# HV_MPPC.net
KiCad netlist of a schematic drawn in EAGLE
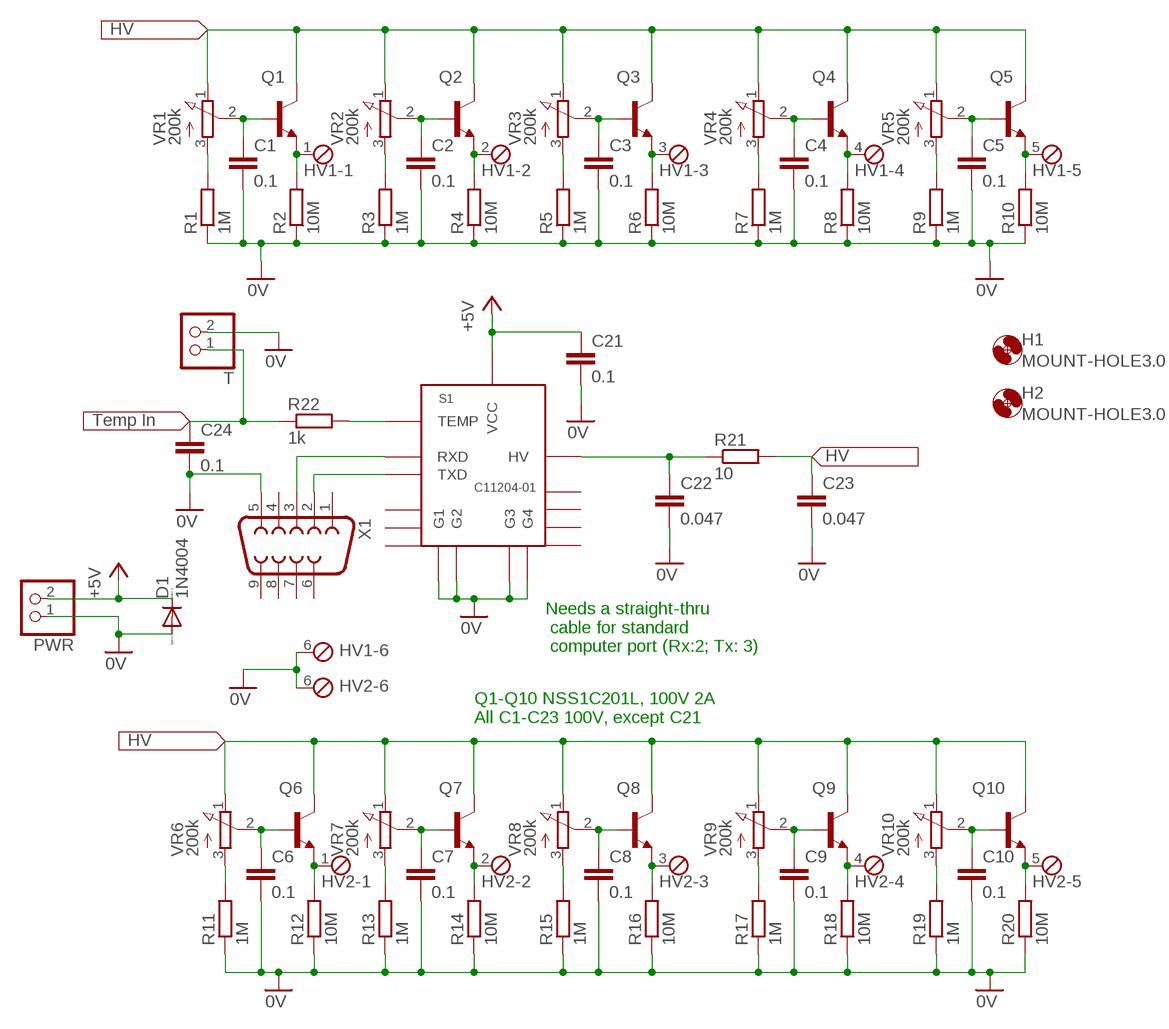
[diagram p0: schematic, sheet 1]

(export (version "E")
  (design (tool "Eeschema 10.0.6"))
  (components
    (comp (ref "C1")
      (value "0.1")
      (footprint "eagle-import:C0805")
      (libsource (lib "eagle-import") (part "C-EUC0805"))
    )
    (comp (ref "C2")
      (value "0.1")
      (footprint "eagle-import:C0805")
      (libsource (lib "eagle-import") (part "C-EUC0805"))
    )
    (comp (ref "C3")
      (value "0.1")
      (footprint "eagle-import:C0805")
      (libsource (lib "eagle-import") (part "C-EUC0805"))
    )
    (comp (ref "C4")
      (value "0.1")
      (footprint "eagle-import:C0805")
      (libsource (lib "eagle-import") (part "C-EUC0805"))
    )
    (comp (ref "C5")
      (value "0.1")
      (footprint "eagle-import:C0805")
      (libsource (lib "eagle-import") (part "C-EUC0805"))
    )
    (comp (ref "C6")
      (value "0.1")
      (footprint "eagle-import:C0805")
      (libsource (lib "eagle-import") (part "C-EUC0805"))
    )
    (comp (ref "C7")
      (value "0.1")
      (footprint "eagle-import:C0805")
      (libsource (lib "eagle-import") (part "C-EUC0805"))
    )
    (comp (ref "C8")
      (value "0.1")
      (footprint "eagle-import:C0805")
      (libsource (lib "eagle-import") (part "C-EUC0805"))
    )
    (comp (ref "C9")
      (value "0.1")
      (footprint "eagle-import:C0805")
      (libsource (lib "eagle-import") (part "C-EUC0805"))
    )
    (comp (ref "C10")
      (value "0.1")
      (footprint "eagle-import:C0805")
      (libsource (lib "eagle-import") (part "C-EUC0805"))
    )
    (comp (ref "C21")
      (value "0.1")
      (footprint "eagle-import:C0805")
      (libsource (lib "eagle-import") (part "C-EUC0805"))
    )
    (comp (ref "C22")
      (value "0.047")
      (footprint "eagle-import:C0805")
      (libsource (lib "eagle-import") (part "C-EUC0805"))
    )
    (comp (ref "C23")
      (value "0.047")
      (footprint "eagle-import:C0805")
      (libsource (lib "eagle-import") (part "C-EUC0805"))
    )
    (comp (ref "C24")
      (value "0.1")
      (footprint "eagle-import:C0805")
      (libsource (lib "eagle-import") (part "C-EUC0805"))
    )
    (comp (ref "D1")
      (value "1N4004")
      (footprint "eagle-import:DO41-10")
      (libsource (lib "eagle-import") (part "1N4004"))
    )
    (comp (ref "H1")
      (value "MOUNT-HOLE3.0")
      (footprint "eagle-import:3,0")
      (libsource (lib "eagle-import") (part "MOUNT-HOLE3.0"))
    )
    (comp (ref "H2")
      (value "MOUNT-HOLE3.0")
      (footprint "eagle-import:3,0")
      (libsource (lib "eagle-import") (part "MOUNT-HOLE3.0"))
    )
    (comp (ref "HV1")
      (value "MPT6")
      (footprint "eagle-import:6POL254")
      (libsource (lib "eagle-import") (part "MPT6"))
    )
    (comp (ref "HV2")
      (value "MPT6")
      (footprint "eagle-import:6POL254")
      (libsource (lib "eagle-import") (part "MPT6"))
    )
    (comp (ref "PWR")
      (value "PINHD-1X2")
      (footprint "eagle-import:1X02")
      (libsource (lib "eagle-import") (part "PINHD-1X2"))
    )
    (comp (ref "Q1")
      (value "NSS1C201L")
      (footprint "eagle-import:SOT23")
      (libsource (lib "eagle-import") (part "NSS1C201L"))
    )
    (comp (ref "Q2")
      (value "NSS1C201L")
      (footprint "eagle-import:SOT23")
      (libsource (lib "eagle-import") (part "NSS1C201L"))
    )
    (comp (ref "Q3")
      (value "NSS1C201L")
      (footprint "eagle-import:SOT23")
      (libsource (lib "eagle-import") (part "NSS1C201L"))
    )
    (comp (ref "Q4")
      (value "NSS1C201L")
      (footprint "eagle-import:SOT23")
      (libsource (lib "eagle-import") (part "NSS1C201L"))
    )
    (comp (ref "Q5")
      (value "NSS1C201L")
      (footprint "eagle-import:SOT23")
      (libsource (lib "eagle-import") (part "NSS1C201L"))
    )
    (comp (ref "Q6")
      (value "NSS1C201L")
      (footprint "eagle-import:SOT23")
      (libsource (lib "eagle-import") (part "NSS1C201L"))
    )
    (comp (ref "Q7")
      (value "NSS1C201L")
      (footprint "eagle-import:SOT23")
      (libsource (lib "eagle-import") (part "NSS1C201L"))
    )
    (comp (ref "Q8")
      (value "NSS1C201L")
      (footprint "eagle-import:SOT23")
      (libsource (lib "eagle-import") (part "NSS1C201L"))
    )
    (comp (ref "Q9")
      (value "NSS1C201L")
      (footprint "eagle-import:SOT23")
      (libsource (lib "eagle-import") (part "NSS1C201L"))
    )
    (comp (ref "Q10")
      (value "NSS1C201L")
      (footprint "eagle-import:SOT23")
      (libsource (lib "eagle-import") (part "NSS1C201L"))
    )
    (comp (ref "R1")
      (value "1M")
      (footprint "eagle-import:R0805")
      (libsource (lib "eagle-import") (part "R-EU_R0805"))
    )
    (comp (ref "R2")
      (value "10M")
      (footprint "eagle-import:R0805")
      (libsource (lib "eagle-import") (part "R-EU_R0805"))
    )
    (comp (ref "R3")
      (value "1M")
      (footprint "eagle-import:R0805")
      (libsource (lib "eagle-import") (part "R-EU_R0805"))
    )
    (comp (ref "R4")
      (value "10M")
      (footprint "eagle-import:R0805")
      (libsource (lib "eagle-import") (part "R-EU_R0805"))
    )
    (comp (ref "R5")
      (value "1M")
      (footprint "eagle-import:R0805")
      (libsource (lib "eagle-import") (part "R-EU_R0805"))
    )
    (comp (ref "R6")
      (value "10M")
      (footprint "eagle-import:R0805")
      (libsource (lib "eagle-import") (part "R-EU_R0805"))
    )
    (comp (ref "R7")
      (value "1M")
      (footprint "eagle-import:R0805")
      (libsource (lib "eagle-import") (part "R-EU_R0805"))
    )
    (comp (ref "R8")
      (value "10M")
      (footprint "eagle-import:R0805")
      (libsource (lib "eagle-import") (part "R-EU_R0805"))
    )
    (comp (ref "R9")
      (value "1M")
      (footprint "eagle-import:R0805")
      (libsource (lib "eagle-import") (part "R-EU_R0805"))
    )
    (comp (ref "R10")
      (value "10M")
      (footprint "eagle-import:R0805")
      (libsource (lib "eagle-import") (part "R-EU_R0805"))
    )
    (comp (ref "R11")
      (value "1M")
      (footprint "eagle-import:R0805")
      (libsource (lib "eagle-import") (part "R-EU_R0805"))
    )
    (comp (ref "R12")
      (value "10M")
      (footprint "eagle-import:R0805")
      (libsource (lib "eagle-import") (part "R-EU_R0805"))
    )
    (comp (ref "R13")
      (value "1M")
      (footprint "eagle-import:R0805")
      (libsource (lib "eagle-import") (part "R-EU_R0805"))
    )
    (comp (ref "R14")
      (value "10M")
      (footprint "eagle-import:R0805")
      (libsource (lib "eagle-import") (part "R-EU_R0805"))
    )
    (comp (ref "R15")
      (value "1M")
      (footprint "eagle-import:R0805")
      (libsource (lib "eagle-import") (part "R-EU_R0805"))
    )
    (comp (ref "R16")
      (value "10M")
      (footprint "eagle-import:R0805")
      (libsource (lib "eagle-import") (part "R-EU_R0805"))
    )
    (comp (ref "R17")
      (value "1M")
      (footprint "eagle-import:R0805")
      (libsource (lib "eagle-import") (part "R-EU_R0805"))
    )
    (comp (ref "R18")
      (value "10M")
      (footprint "eagle-import:R0805")
      (libsource (lib "eagle-import") (part "R-EU_R0805"))
    )
    (comp (ref "R19")
      (value "1M")
      (footprint "eagle-import:R0805")
      (libsource (lib "eagle-import") (part "R-EU_R0805"))
    )
    (comp (ref "R20")
      (value "10M")
      (footprint "eagle-import:R0805")
      (libsource (lib "eagle-import") (part "R-EU_R0805"))
    )
    (comp (ref "R21")
      (value "10")
      (footprint "eagle-import:R0805")
      (libsource (lib "eagle-import") (part "R-EU_R0805"))
    )
    (comp (ref "R22")
      (value "1k")
      (footprint "eagle-import:R0805")
      (libsource (lib "eagle-import") (part "R-EU_R0805"))
    )
    (comp (ref "S1")
      (value "C11204-01")
      (footprint "eagle-import:C11204-01")
      (libsource (lib "eagle-import") (part "C11204-01"))
    )
    (comp (ref "T")
      (value "PINHD-1X2")
      (footprint "eagle-import:1X02")
      (libsource (lib "eagle-import") (part "PINHD-1X2"))
    )
    (comp (ref "VR1")
      (value "200k")
      (footprint "eagle-import:3314G")
      (libsource (lib "eagle-import") (part "BOURNS3314"))
    )
    (comp (ref "VR2")
      (value "200k")
      (footprint "eagle-import:3314G")
      (libsource (lib "eagle-import") (part "BOURNS3314"))
    )
    (comp (ref "VR3")
      (value "200k")
      (footprint "eagle-import:3314G")
      (libsource (lib "eagle-import") (part "BOURNS3314"))
    )
    (comp (ref "VR4")
      (value "200k")
      (footprint "eagle-import:3314G")
      (libsource (lib "eagle-import") (part "BOURNS3314"))
    )
    (comp (ref "VR5")
      (value "200k")
      (footprint "eagle-import:3314G")
      (libsource (lib "eagle-import") (part "BOURNS3314"))
    )
    (comp (ref "VR6")
      (value "200k")
      (footprint "eagle-import:3314G")
      (libsource (lib "eagle-import") (part "BOURNS3314"))
    )
    (comp (ref "VR7")
      (value "200k")
      (footprint "eagle-import:3314G")
      (libsource (lib "eagle-import") (part "BOURNS3314"))
    )
    (comp (ref "VR8")
      (value "200k")
      (footprint "eagle-import:3314G")
      (libsource (lib "eagle-import") (part "BOURNS3314"))
    )
    (comp (ref "VR9")
      (value "200k")
      (footprint "eagle-import:3314G")
      (libsource (lib "eagle-import") (part "BOURNS3314"))
    )
    (comp (ref "VR10")
      (value "200k")
      (footprint "eagle-import:3314G")
      (libsource (lib "eagle-import") (part "BOURNS3314"))
    )
    (comp (ref "X1")
      (value "F09HP")
      (footprint "eagle-import:F09HP")
      (libsource (lib "eagle-import") (part "F09HP"))
    )
  )
  (nets
    (net (code "1") (name "+5V") (class "Default")
      (node (ref "C21") (pin "1") (pinfunction "1_1") (pintype "passive"))
      (node (ref "D1") (pin "C") (pinfunction "C_C") (pintype "passive"))
      (node (ref "PWR") (pin "2") (pinfunction "2_2") (pintype "passive"))
      (node (ref "S1") (pin "P$1") (pinfunction "VCC_P$1") (pintype "power_in"))
    )
    (net (code "2") (name "/HVOUT") (class "Default")
      (node (ref "C23") (pin "1") (pinfunction "1_1") (pintype "passive"))
      (node (ref "Q1") (pin "3") (pinfunction "C_3") (pintype "passive"))
      (node (ref "Q10") (pin "3") (pinfunction "C_3") (pintype "passive"))
      (node (ref "Q2") (pin "3") (pinfunction "C_3") (pintype "passive"))
      (node (ref "Q3") (pin "3") (pinfunction "C_3") (pintype "passive"))
      (node (ref "Q4") (pin "3") (pinfunction "C_3") (pintype "passive"))
      (node (ref "Q5") (pin "3") (pinfunction "C_3") (pintype "passive"))
      (node (ref "Q6") (pin "3") (pinfunction "C_3") (pintype "passive"))
      (node (ref "Q7") (pin "3") (pinfunction "C_3") (pintype "passive"))
      (node (ref "Q8") (pin "3") (pinfunction "C_3") (pintype "passive"))
      (node (ref "Q9") (pin "3") (pinfunction "C_3") (pintype "passive"))
      (node (ref "R21") (pin "2") (pinfunction "2_2") (pintype "passive"))
      (node (ref "VR1") (pin "1") (pinfunction "E_1") (pintype "passive"))
      (node (ref "VR10") (pin "1") (pinfunction "E_1") (pintype "passive"))
      (node (ref "VR2") (pin "1") (pinfunction "E_1") (pintype "passive"))
      (node (ref "VR3") (pin "1") (pinfunction "E_1") (pintype "passive"))
      (node (ref "VR4") (pin "1") (pinfunction "E_1") (pintype "passive"))
      (node (ref "VR5") (pin "1") (pinfunction "E_1") (pintype "passive"))
      (node (ref "VR6") (pin "1") (pinfunction "E_1") (pintype "passive"))
      (node (ref "VR7") (pin "1") (pinfunction "E_1") (pintype "passive"))
      (node (ref "VR8") (pin "1") (pinfunction "E_1") (pintype "passive"))
      (node (ref "VR9") (pin "1") (pinfunction "E_1") (pintype "passive"))
    )
    (net (code "3") (name "0V") (class "Default")
      (node (ref "C1") (pin "2") (pinfunction "2_2") (pintype "passive"))
      (node (ref "C10") (pin "2") (pinfunction "2_2") (pintype "passive"))
      (node (ref "C2") (pin "2") (pinfunction "2_2") (pintype "passive"))
      (node (ref "C21") (pin "2") (pinfunction "2_2") (pintype "passive"))
      (node (ref "C22") (pin "2") (pinfunction "2_2") (pintype "passive"))
      (node (ref "C23") (pin "2") (pinfunction "2_2") (pintype "passive"))
      (node (ref "C24") (pin "2") (pinfunction "2_2") (pintype "passive"))
      (node (ref "C3") (pin "2") (pinfunction "2_2") (pintype "passive"))
      (node (ref "C4") (pin "2") (pinfunction "2_2") (pintype "passive"))
      (node (ref "C5") (pin "2") (pinfunction "2_2") (pintype "passive"))
      (node (ref "C6") (pin "2") (pinfunction "2_2") (pintype "passive"))
      (node (ref "C7") (pin "2") (pinfunction "2_2") (pintype "passive"))
      (node (ref "C8") (pin "2") (pinfunction "2_2") (pintype "passive"))
      (node (ref "C9") (pin "2") (pinfunction "2_2") (pintype "passive"))
      (node (ref "D1") (pin "A") (pinfunction "A_A") (pintype "passive"))
      (node (ref "HV1") (pin "6") (pinfunction "1_6") (pintype "passive"))
      (node (ref "HV2") (pin "6") (pinfunction "1_6") (pintype "passive"))
      (node (ref "PWR") (pin "1") (pinfunction "1_1") (pintype "passive"))
      (node (ref "R1") (pin "1") (pinfunction "1_1") (pintype "passive"))
      (node (ref "R10") (pin "1") (pinfunction "1_1") (pintype "passive"))
      (node (ref "R11") (pin "1") (pinfunction "1_1") (pintype "passive"))
      (node (ref "R12") (pin "1") (pinfunction "1_1") (pintype "passive"))
      (node (ref "R13") (pin "1") (pinfunction "1_1") (pintype "passive"))
      (node (ref "R14") (pin "1") (pinfunction "1_1") (pintype "passive"))
      (node (ref "R15") (pin "1") (pinfunction "1_1") (pintype "passive"))
      (node (ref "R16") (pin "1") (pinfunction "1_1") (pintype "passive"))
      (node (ref "R17") (pin "1") (pinfunction "1_1") (pintype "passive"))
      (node (ref "R18") (pin "1") (pinfunction "1_1") (pintype "passive"))
      (node (ref "R19") (pin "1") (pinfunction "1_1") (pintype "passive"))
      (node (ref "R2") (pin "1") (pinfunction "1_1") (pintype "passive"))
      (node (ref "R20") (pin "1") (pinfunction "1_1") (pintype "passive"))
      (node (ref "R3") (pin "1") (pinfunction "1_1") (pintype "passive"))
      (node (ref "R4") (pin "1") (pinfunction "1_1") (pintype "passive"))
      (node (ref "R5") (pin "1") (pinfunction "1_1") (pintype "passive"))
      (node (ref "R6") (pin "1") (pinfunction "1_1") (pintype "passive"))
      (node (ref "R7") (pin "1") (pinfunction "1_1") (pintype "passive"))
      (node (ref "R8") (pin "1") (pinfunction "1_1") (pintype "passive"))
      (node (ref "R9") (pin "1") (pinfunction "1_1") (pintype "passive"))
      (node (ref "S1") (pin "P$15") (pinfunction "G4_P$15") (pintype "power_in"))
      (node (ref "S1") (pin "P$2") (pinfunction "G1_P$2") (pintype "power_in"))
      (node (ref "S1") (pin "P$5") (pinfunction "G2_P$5") (pintype "power_in"))
      (node (ref "S1") (pin "P$8") (pinfunction "G3_P$8") (pintype "power_in"))
      (node (ref "T") (pin "2") (pinfunction "2_2") (pintype "passive"))
      (node (ref "X1") (pin "5") (pinfunction "5_5") (pintype "passive"))
    )
    (net (code "4") (name "Net-(C24-Pad1)") (class "Default")
      (node (ref "C24") (pin "1") (pinfunction "1_1") (pintype "passive"))
      (node (ref "R22") (pin "1") (pinfunction "1_1") (pintype "passive"))
      (node (ref "T") (pin "1") (pinfunction "1_1") (pintype "passive"))
    )
    (net (code "5") (name "Net-(HV1B-1)") (class "Default")
      (node (ref "HV1") (pin "2") (pinfunction "1_2") (pintype "passive"))
      (node (ref "Q2") (pin "2") (pinfunction "E_2") (pintype "passive"))
      (node (ref "R4") (pin "2") (pinfunction "2_2") (pintype "passive"))
    )
    (net (code "6") (name "Net-(HV1C-1)") (class "Default")
      (node (ref "HV1") (pin "3") (pinfunction "1_3") (pintype "passive"))
      (node (ref "Q3") (pin "2") (pinfunction "E_2") (pintype "passive"))
      (node (ref "R6") (pin "2") (pinfunction "2_2") (pintype "passive"))
    )
    (net (code "7") (name "Net-(HV1D-1)") (class "Default")
      (node (ref "HV1") (pin "4") (pinfunction "1_4") (pintype "passive"))
      (node (ref "Q4") (pin "2") (pinfunction "E_2") (pintype "passive"))
      (node (ref "R8") (pin "2") (pinfunction "2_2") (pintype "passive"))
    )
    (net (code "8") (name "Net-(HV1E-1)") (class "Default")
      (node (ref "HV1") (pin "5") (pinfunction "1_5") (pintype "passive"))
      (node (ref "Q5") (pin "2") (pinfunction "E_2") (pintype "passive"))
      (node (ref "R10") (pin "2") (pinfunction "2_2") (pintype "passive"))
    )
    (net (code "9") (name "Net-(HV2B-1)") (class "Default")
      (node (ref "HV2") (pin "2") (pinfunction "1_2") (pintype "passive"))
      (node (ref "Q7") (pin "2") (pinfunction "E_2") (pintype "passive"))
      (node (ref "R14") (pin "2") (pinfunction "2_2") (pintype "passive"))
    )
    (net (code "10") (name "Net-(HV2C-1)") (class "Default")
      (node (ref "HV2") (pin "3") (pinfunction "1_3") (pintype "passive"))
      (node (ref "Q8") (pin "2") (pinfunction "E_2") (pintype "passive"))
      (node (ref "R16") (pin "2") (pinfunction "2_2") (pintype "passive"))
    )
    (net (code "11") (name "Net-(HV2D-1)") (class "Default")
      (node (ref "HV2") (pin "4") (pinfunction "1_4") (pintype "passive"))
      (node (ref "Q9") (pin "2") (pinfunction "E_2") (pintype "passive"))
      (node (ref "R18") (pin "2") (pinfunction "2_2") (pintype "passive"))
    )
    (net (code "12") (name "Net-(HV2E-1)") (class "Default")
      (node (ref "HV2") (pin "5") (pinfunction "1_5") (pintype "passive"))
      (node (ref "Q10") (pin "2") (pinfunction "E_2") (pintype "passive"))
      (node (ref "R20") (pin "2") (pinfunction "2_2") (pintype "passive"))
    )
    (net (code "13") (name "Net-(Q1-B)") (class "Default")
      (node (ref "C1") (pin "1") (pinfunction "1_1") (pintype "passive"))
      (node (ref "Q1") (pin "1") (pinfunction "B_1") (pintype "passive"))
      (node (ref "VR1") (pin "2") (pinfunction "S_2") (pintype "passive"))
    )
    (net (code "14") (name "Net-(Q1-E)") (class "Default")
      (node (ref "HV1") (pin "1") (pinfunction "1_1") (pintype "passive"))
      (node (ref "Q1") (pin "2") (pinfunction "E_2") (pintype "passive"))
      (node (ref "R2") (pin "2") (pinfunction "2_2") (pintype "passive"))
    )
    (net (code "15") (name "Net-(Q2-B)") (class "Default")
      (node (ref "C2") (pin "1") (pinfunction "1_1") (pintype "passive"))
      (node (ref "Q2") (pin "1") (pinfunction "B_1") (pintype "passive"))
      (node (ref "VR2") (pin "2") (pinfunction "S_2") (pintype "passive"))
    )
    (net (code "16") (name "Net-(Q3-B)") (class "Default")
      (node (ref "C3") (pin "1") (pinfunction "1_1") (pintype "passive"))
      (node (ref "Q3") (pin "1") (pinfunction "B_1") (pintype "passive"))
      (node (ref "VR3") (pin "2") (pinfunction "S_2") (pintype "passive"))
    )
    (net (code "17") (name "Net-(Q4-B)") (class "Default")
      (node (ref "C4") (pin "1") (pinfunction "1_1") (pintype "passive"))
      (node (ref "Q4") (pin "1") (pinfunction "B_1") (pintype "passive"))
      (node (ref "VR4") (pin "2") (pinfunction "S_2") (pintype "passive"))
    )
    (net (code "18") (name "Net-(Q5-B)") (class "Default")
      (node (ref "C5") (pin "1") (pinfunction "1_1") (pintype "passive"))
      (node (ref "Q5") (pin "1") (pinfunction "B_1") (pintype "passive"))
      (node (ref "VR5") (pin "2") (pinfunction "S_2") (pintype "passive"))
    )
    (net (code "19") (name "Net-(Q6-B)") (class "Default")
      (node (ref "C6") (pin "1") (pinfunction "1_1") (pintype "passive"))
      (node (ref "Q6") (pin "1") (pinfunction "B_1") (pintype "passive"))
      (node (ref "VR6") (pin "2") (pinfunction "S_2") (pintype "passive"))
    )
    (net (code "20") (name "Net-(Q6-E)") (class "Default")
      (node (ref "HV2") (pin "1") (pinfunction "1_1") (pintype "passive"))
      (node (ref "Q6") (pin "2") (pinfunction "E_2") (pintype "passive"))
      (node (ref "R12") (pin "2") (pinfunction "2_2") (pintype "passive"))
    )
    (net (code "21") (name "Net-(Q7-B)") (class "Default")
      (node (ref "C7") (pin "1") (pinfunction "1_1") (pintype "passive"))
      (node (ref "Q7") (pin "1") (pinfunction "B_1") (pintype "passive"))
      (node (ref "VR7") (pin "2") (pinfunction "S_2") (pintype "passive"))
    )
    (net (code "22") (name "Net-(Q8-B)") (class "Default")
      (node (ref "C8") (pin "1") (pinfunction "1_1") (pintype "passive"))
      (node (ref "Q8") (pin "1") (pinfunction "B_1") (pintype "passive"))
      (node (ref "VR8") (pin "2") (pinfunction "S_2") (pintype "passive"))
    )
    (net (code "23") (name "Net-(Q9-B)") (class "Default")
      (node (ref "C9") (pin "1") (pinfunction "1_1") (pintype "passive"))
      (node (ref "Q9") (pin "1") (pinfunction "B_1") (pintype "passive"))
      (node (ref "VR9") (pin "2") (pinfunction "S_2") (pintype "passive"))
    )
    (net (code "24") (name "Net-(Q10-B)") (class "Default")
      (node (ref "C10") (pin "1") (pinfunction "1_1") (pintype "passive"))
      (node (ref "Q10") (pin "1") (pinfunction "B_1") (pintype "passive"))
      (node (ref "VR10") (pin "2") (pinfunction "S_2") (pintype "passive"))
    )
    (net (code "25") (name "Net-(S1-HV)") (class "Default")
      (node (ref "C22") (pin "1") (pinfunction "1_1") (pintype "passive"))
      (node (ref "R21") (pin "1") (pinfunction "1_1") (pintype "passive"))
      (node (ref "S1") (pin "P$10") (pinfunction "HV_P$10") (pintype "power_in"))
    )
    (net (code "26") (name "Net-(S1-RXD)") (class "Default")
      (node (ref "S1") (pin "P$3") (pinfunction "RXD_P$3") (pintype "input"))
      (node (ref "X1") (pin "3") (pinfunction "3_3") (pintype "passive"))
    )
    (net (code "27") (name "Net-(S1-TEMP)") (class "Default")
      (node (ref "R22") (pin "2") (pinfunction "2_2") (pintype "passive"))
      (node (ref "S1") (pin "P$16") (pinfunction "TEMP_P$16") (pintype "input"))
    )
    (net (code "28") (name "Net-(S1-TXD)") (class "Default")
      (node (ref "S1") (pin "P$4") (pinfunction "TXD_P$4") (pintype "output"))
      (node (ref "X1") (pin "2") (pinfunction "2_2") (pintype "passive"))
    )
    (net (code "29") (name "Net-(VR1-A)") (class "Default")
      (node (ref "R1") (pin "2") (pinfunction "2_2") (pintype "passive"))
      (node (ref "VR1") (pin "3") (pinfunction "A_3") (pintype "passive"))
    )
    (net (code "30") (name "Net-(VR2-A)") (class "Default")
      (node (ref "R3") (pin "2") (pinfunction "2_2") (pintype "passive"))
      (node (ref "VR2") (pin "3") (pinfunction "A_3") (pintype "passive"))
    )
    (net (code "31") (name "Net-(VR3-A)") (class "Default")
      (node (ref "R5") (pin "2") (pinfunction "2_2") (pintype "passive"))
      (node (ref "VR3") (pin "3") (pinfunction "A_3") (pintype "passive"))
    )
    (net (code "32") (name "Net-(VR4-A)") (class "Default")
      (node (ref "R7") (pin "2") (pinfunction "2_2") (pintype "passive"))
      (node (ref "VR4") (pin "3") (pinfunction "A_3") (pintype "passive"))
    )
    (net (code "33") (name "Net-(VR5-A)") (class "Default")
      (node (ref "R9") (pin "2") (pinfunction "2_2") (pintype "passive"))
      (node (ref "VR5") (pin "3") (pinfunction "A_3") (pintype "passive"))
    )
    (net (code "34") (name "Net-(VR6-A)") (class "Default")
      (node (ref "R11") (pin "2") (pinfunction "2_2") (pintype "passive"))
      (node (ref "VR6") (pin "3") (pinfunction "A_3") (pintype "passive"))
    )
    (net (code "35") (name "Net-(VR7-A)") (class "Default")
      (node (ref "R13") (pin "2") (pinfunction "2_2") (pintype "passive"))
      (node (ref "VR7") (pin "3") (pinfunction "A_3") (pintype "passive"))
    )
    (net (code "36") (name "Net-(VR8-A)") (class "Default")
      (node (ref "R15") (pin "2") (pinfunction "2_2") (pintype "passive"))
      (node (ref "VR8") (pin "3") (pinfunction "A_3") (pintype "passive"))
    )
    (net (code "37") (name "Net-(VR9-A)") (class "Default")
      (node (ref "R17") (pin "2") (pinfunction "2_2") (pintype "passive"))
      (node (ref "VR9") (pin "3") (pinfunction "A_3") (pintype "passive"))
    )
    (net (code "38") (name "Net-(VR10-A)") (class "Default")
      (node (ref "R19") (pin "2") (pinfunction "2_2") (pintype "passive"))
      (node (ref "VR10") (pin "3") (pinfunction "A_3") (pintype "passive"))
    )
    (net (code "39") (name "unconnected-(S1-PadP$6)") (class "Default")
      (node (ref "S1") (pin "P$6") (pinfunction "P$6_P$6") (pintype "no_connect"))
    )
    (net (code "40") (name "unconnected-(S1-PadP$7)") (class "Default")
      (node (ref "S1") (pin "P$7") (pinfunction "P$7_P$7") (pintype "no_connect"))
    )
    (net (code "41") (name "unconnected-(S1-PadP$9)") (class "Default")
      (node (ref "S1") (pin "P$9") (pinfunction "P$9_P$9") (pintype "no_connect"))
    )
    (net (code "42") (name "unconnected-(S1-PadP$11)") (class "Default")
      (node (ref "S1") (pin "P$11") (pinfunction "P$11_P$11") (pintype "no_connect"))
    )
    (net (code "43") (name "unconnected-(S1-PadP$12)") (class "Default")
      (node (ref "S1") (pin "P$12") (pinfunction "P$12_P$12") (pintype "no_connect"))
    )
    (net (code "44") (name "unconnected-(S1-PadP$13)") (class "Default")
      (node (ref "S1") (pin "P$13") (pinfunction "P$13_P$13") (pintype "no_connect"))
    )
    (net (code "45") (name "unconnected-(S1-PadP$14)") (class "Default")
      (node (ref "S1") (pin "P$14") (pinfunction "P$14_P$14") (pintype "no_connect"))
    )
    (net (code "46") (name "unconnected-(X1-Pad1)") (class "Default")
      (node (ref "X1") (pin "1") (pinfunction "1_1") (pintype "passive"))
    )
    (net (code "47") (name "unconnected-(X1-Pad4)") (class "Default")
      (node (ref "X1") (pin "4") (pinfunction "4_4") (pintype "passive"))
    )
    (net (code "48") (name "unconnected-(X1-Pad6)") (class "Default")
      (node (ref "X1") (pin "6") (pinfunction "6_6") (pintype "passive"))
    )
    (net (code "49") (name "unconnected-(X1-Pad7)") (class "Default")
      (node (ref "X1") (pin "7") (pinfunction "7_7") (pintype "passive"))
    )
    (net (code "50") (name "unconnected-(X1-Pad8)") (class "Default")
      (node (ref "X1") (pin "8") (pinfunction "8_8") (pintype "passive"))
    )
    (net (code "51") (name "unconnected-(X1-Pad9)") (class "Default")
      (node (ref "X1") (pin "9") (pinfunction "9_9") (pintype "passive"))
    )
  )
)
